# Power_Schematic.net
KiCad netlist of a schematic drawn in Altium Designer
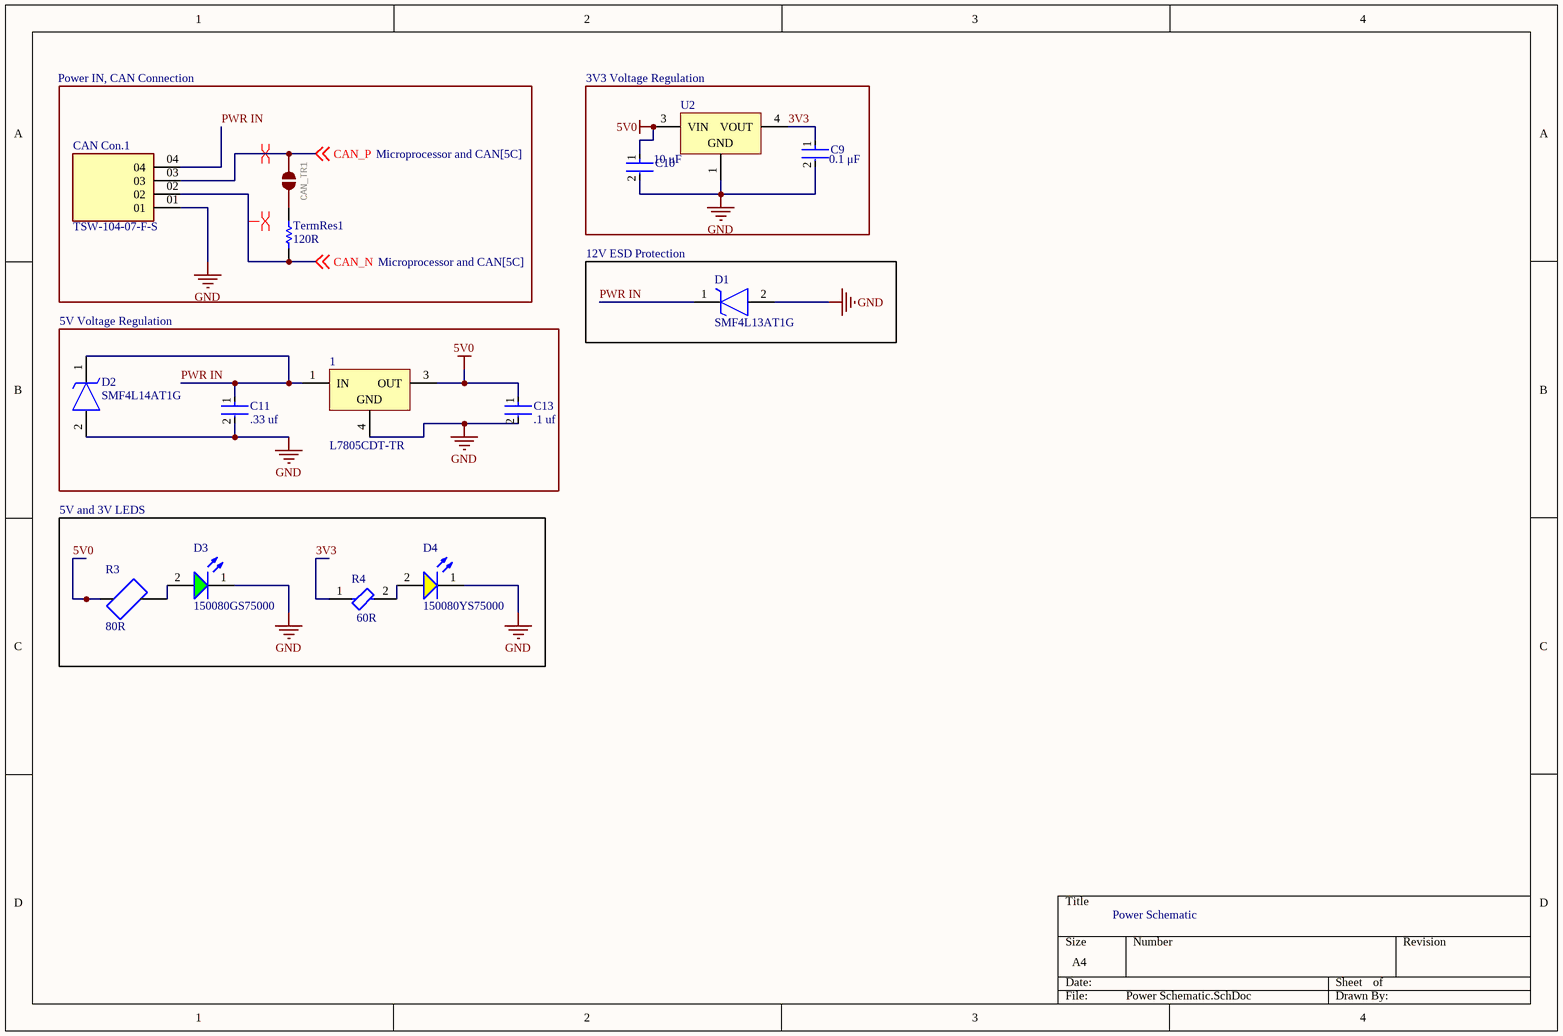
[diagram p0: Power Schematic.SchDoc]

(export (version "E")
  (design (tool "Eeschema 10.0.6"))
  (components
    (comp (ref "1")
      (value "L7805CDT-TR")
      (footprint "TO-252_N")
      (description "Positive Voltage Regulator, 3-Pin DPAK, Tape and Reel")
      (libsource (lib "Altium Content Vault") (part "PM-REG-L4940-SOT3"))
    )
    (comp (ref "C9")
      (value "C0805C106K8PACTU")
      (footprint "FP-C0805C-DG-MFG")
      (description "CAP CER 10UF 10V X5R 0805")
      (fields (field (name "TOLERANCE") "10%") (field (name "MANUFACTURER") "Kemet"))
      (libsource (lib "Altium Content Vault") (part "11868f565c42a9108669ba33697ecf6"))
    )
    (comp (ref "C10")
      (value "08051C104K4T2A")
      (footprint "FP-0805-L_2_01_0_2-W_1_25-IPC_B")
      (description "Automotive Ceramic Capacitor, 0805, 100nF, 10%, X7R, 15%, 100V")
      (fields (field (name "TOLERANCE") "10%") (field (name "VOLTAGE") "100V"))
      (libsource (lib "Altium Content Vault") (part "b4654b650e69147ec39a6b967a45e02"))
    )
    (comp (ref "C11")
      (value ".33 uf")
      (footprint "FP-GCJ219-0_3-IPC_A")
      (description "Cap Ceramic Multilayer 0.33uF 50VDC 10% SMD Paper T/R")
      (fields (field (name "TOLERANCE") "10%"))
      (libsource (lib "Altium Content Vault") (part "02cd4be3c70576c341d710602a673aa"))
    )
    (comp (ref "C13")
      (value ".1 uf")
      (footprint "FP-0805-L_2_01_0_2-W_1_25-IPC_B")
      (description "General Purpose Ceramic Capacitor, 0805, 100nF, 10%, X7R, 15%, 100V")
      (fields (field (name "VOLTAGE") "100V") (field (name "TOLERANCE") "10%"))
      (libsource (lib "Altium Content Vault") (part "b4654b650e69147ec39a6b967a45e02"))
    )
    (comp (ref "CAN Con.1")
      (value "TSW-104-07-F-S")
      (footprint "SAMTEC_TSW-104-07-F-S")
      (fields (field (name "MF") "Samtec"))
      (libsource (lib "TSW-104-07-F-S") (part "TSW-104-07-F-S"))
    )
    (comp (ref "CAN_TR1")
      (value "~")
      (footprint "SMT-JUMPER_2_NO_SILK")
      (libsource (lib "SparkFun-Jumpers") (part "JUMPER-SMT_2_NO_SILK"))
    )
    (comp (ref "D1")
      (value "SMF4L13AT1G")
      (footprint "SamacSys:SODFL3619X98N")
      (description "TVS Diode (Uni-directional)")
      (fields (field (name "MOUSER PART NUMBER") "576-SMF4L13AT1G"))
      (libsource (lib "*") (part "SMF4L13AT1G"))
    )
    (comp (ref "D2")
      (value "SMF4L14AT1G")
      (footprint "SamacSys:SODFL3619X98N")
      (description "TVS Diode (Uni-directional)")
      (fields (field (name "MOUSER PART NUMBER") "576-SMF4L14AT1G"))
      (libsource (lib "*") (part "SMF4L14AT1G"))
    )
    (comp (ref "D3")
      (value "150080GS75000")
      (footprint "WL-SMCW_0805_150080xx75000")
      (description "WURTH ELEKTRONIK - 150080GS75000 - LED, Green, SMD, 0805, 30 mA, 3.2 V, 520 nm")
      (libsource (lib "Altium Content Vault") (part "LED_Green_2A-1K"))
    )
    (comp (ref "D4")
      (value "150080YS75000")
      (footprint "WL-SMCW_0805_150080xx75000")
      (description "2 V Yellow LED 2012 (0805) SMD, Wurth Elektronik WL-SMCW 150080YS75000")
      (libsource (lib "Altium Content Vault") (part "LED_Yellow_2A-1K"))
    )
    (comp (ref "R3")
      (value "80R")
      (footprint "HI0805R800R-10:FB_HI0805R800R-10")
      (fields
        (field (name "MF") "{'manufacturer': u'Laird-Signal Integrity Products'}")
        (field (name "MP") "HI0805R800R-10")
      )
      (libsource (lib "*") (part "HI0805R800R-10"))
    )
    (comp (ref "R4")
      (value "60R")
      (footprint "FP-BLM21-0_2-t0_85-e0_5-d-IPC_A")
      (description "Chip Ferrite Bead, 0805, 60Ω @ 100MHz, 0.02Ω, 25%, 3.5A")
      (fields (field (name "TOLERANCE") "25%"))
      (libsource (lib "Altium Content Vault") (part "5f30dd21d616792df468990f7003faa"))
    )
    (comp (ref "TermRes1")
      (value "120R")
      (footprint "RESC2013X60X40LL20T25")
      (fields (field (name "PART NUMBER") "ERA6AEB473V") (field (name "MANUFACTURER") "Panasonic"))
      (libsource (lib "Altium Content Vault") (part "RES"))
    )
    (comp (ref "U2")
      (value "LD1117ADT33TR")
      (footprint "TO-252_L")
      (description "1A, Low Drop Positive Voltage Regulator, 3.3V, 3-Pin DPAK, Tape and Reel")
      (libsource (lib "Altium Content Vault") (part "PM-REG-LD1117-SOT3"))
    )
  )
  (nets
    (net (code "1") (name "/3V3") (class "Default")
      (node (ref "C9") (pin "1") (pinfunction "1_1") (pintype "passive"))
      (node (ref "R4") (pin "1") (pinfunction "1_1") (pintype "passive"))
      (node (ref "U2") (pin "4") (pinfunction "VOUT_4") (pintype "power_in"))
    )
    (net (code "2") (name "/PWR IN") (class "Default")
      (node (ref "1") (pin "1") (pinfunction "IN_1") (pintype "power_in"))
      (node (ref "C11") (pin "1") (pinfunction "1_1") (pintype "passive"))
      (node (ref "CAN Con.1") (pin "04") (pinfunction "04_04") (pintype "passive"))
      (node (ref "D1") (pin "1") (pinfunction "K_1") (pintype "passive"))
      (node (ref "D2") (pin "1") (pinfunction "K_1") (pintype "passive"))
    )
    (net (code "3") (name "5V0") (class "Default")
      (node (ref "1") (pin "3") (pinfunction "OUT_3") (pintype "power_in"))
      (node (ref "C10") (pin "1") (pinfunction "1_1") (pintype "passive"))
      (node (ref "C13") (pin "1") (pinfunction "1_1") (pintype "passive"))
      (node (ref "R3") (pin "1") (pinfunction "1_1") (pintype "passive"))
      (node (ref "U2") (pin "3") (pinfunction "VIN_3") (pintype "power_in"))
    )
    (net (code "4") (name "CAN_N") (class "Default")
      (node (ref "CAN Con.1") (pin "02") (pinfunction "02_02") (pintype "passive"))
      (node (ref "TermRes1") (pin "1") (pinfunction "1_1") (pintype "passive"))
    )
    (net (code "5") (name "CAN_P") (class "Default")
      (node (ref "CAN Con.1") (pin "03") (pinfunction "03_03") (pintype "passive"))
      (node (ref "CAN_TR1") (pin "1") (pinfunction "1_1") (pintype "passive"))
    )
    (net (code "6") (name "GND") (class "Default")
      (node (ref "1") (pin "4") (pinfunction "GND_4") (pintype "power_in"))
      (node (ref "C10") (pin "2") (pinfunction "2_2") (pintype "passive"))
      (node (ref "C11") (pin "2") (pinfunction "2_2") (pintype "passive"))
      (node (ref "C13") (pin "2") (pinfunction "2_2") (pintype "passive"))
      (node (ref "C9") (pin "2") (pinfunction "2_2") (pintype "passive"))
      (node (ref "CAN Con.1") (pin "01") (pinfunction "01_01") (pintype "passive"))
      (node (ref "D1") (pin "2") (pinfunction "A_2") (pintype "passive"))
      (node (ref "D2") (pin "2") (pinfunction "A_2") (pintype "passive"))
      (node (ref "D3") (pin "1") (pinfunction "K_1") (pintype "passive"))
      (node (ref "D4") (pin "1") (pinfunction "K_1") (pintype "passive"))
      (node (ref "U2") (pin "1") (pinfunction "GND_1") (pintype "power_in"))
    )
    (net (code "7") (name "Net-(CAN_TR1-Pad2)") (class "Default")
      (node (ref "CAN_TR1") (pin "2") (pinfunction "2_2") (pintype "passive"))
      (node (ref "TermRes1") (pin "2") (pinfunction "2_2") (pintype "passive"))
    )
    (net (code "8") (name "Net-(D3-A)") (class "Default")
      (node (ref "D3") (pin "2") (pinfunction "A_2") (pintype "passive"))
      (node (ref "R3") (pin "2") (pinfunction "2_2") (pintype "passive"))
    )
    (net (code "9") (name "Net-(D4-A)") (class "Default")
      (node (ref "D4") (pin "2") (pinfunction "A_2") (pintype "passive"))
      (node (ref "R4") (pin "2") (pinfunction "2_2") (pintype "passive"))
    )
  )
)
